# KGGR_M2.net
KiCad netlist of a schematic drawn in EAGLE
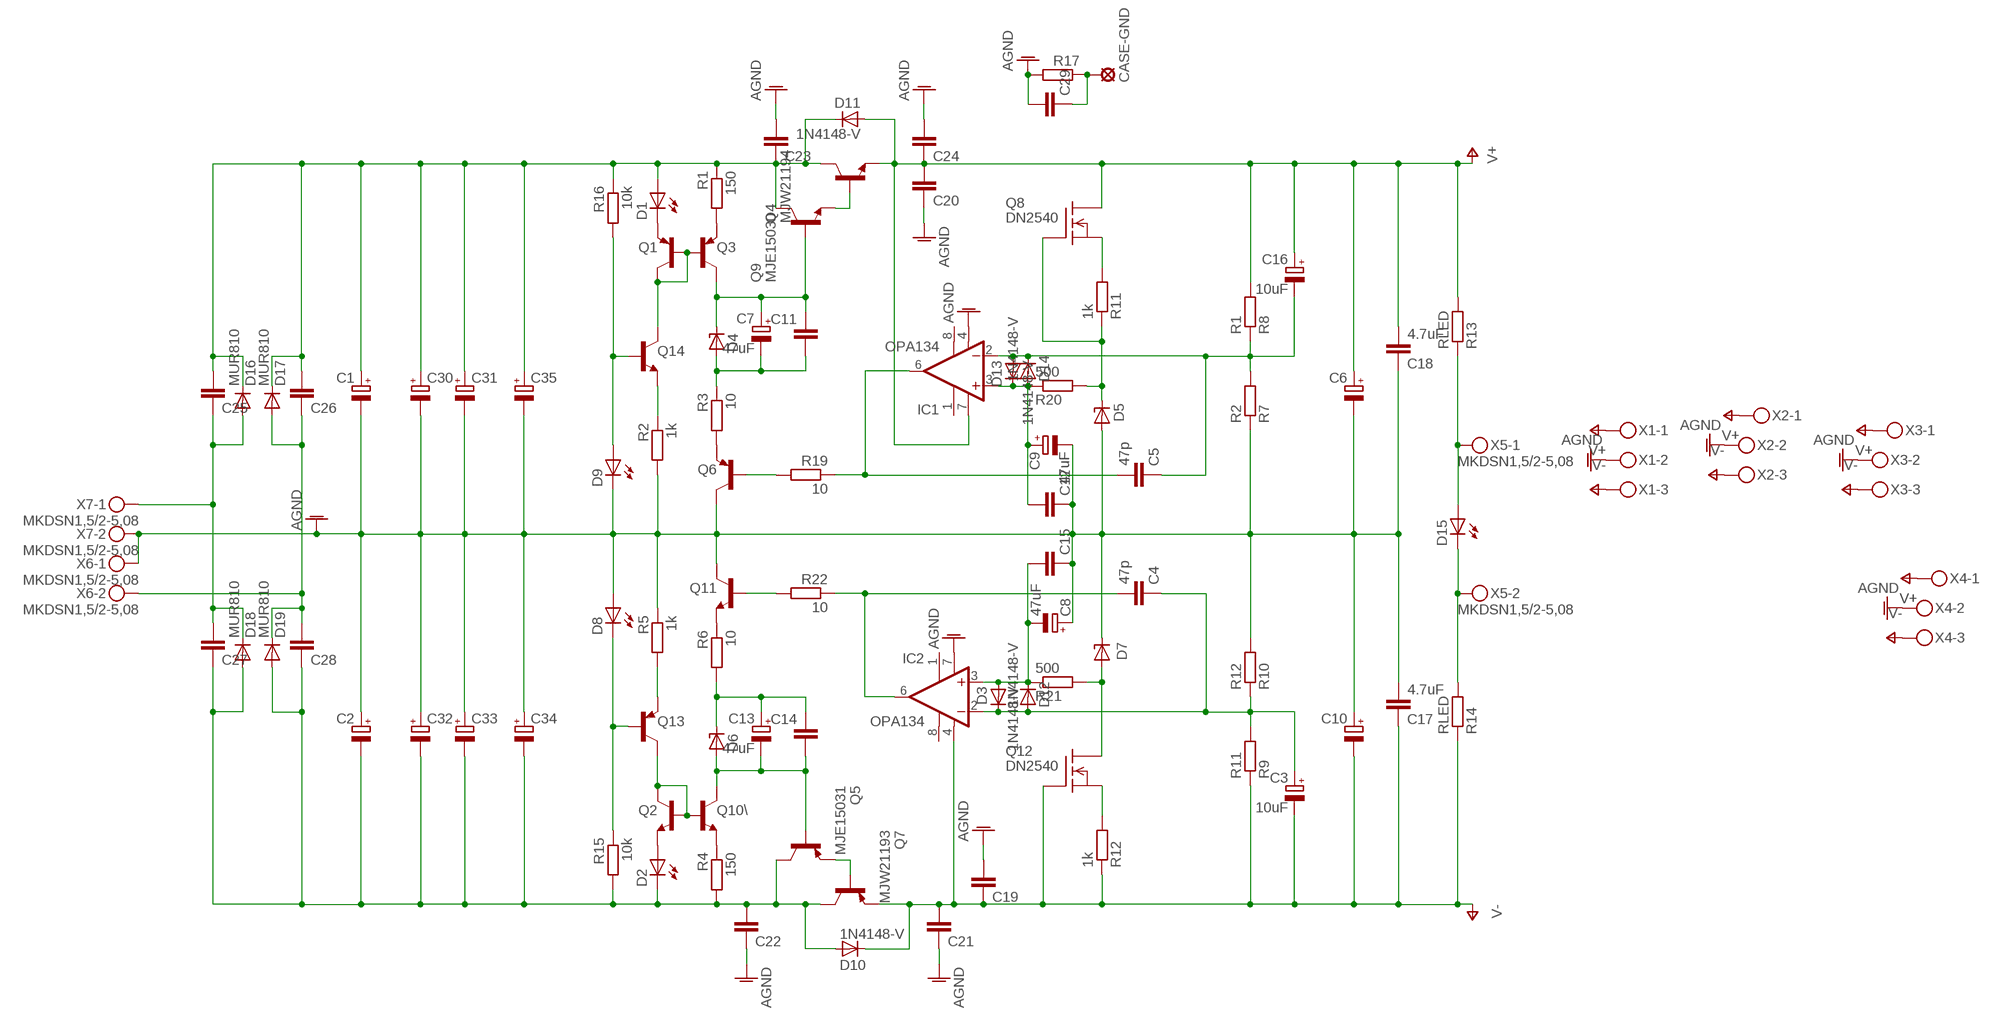
[diagram p0: schematic, sheet 1]

(export (version "E")
  (design (tool "Eeschema 10.0.6"))
  (components
    (comp (ref "C1")
      (value "CPOL-EUE10-35")
      (footprint "eagle-import:EB35D")
      (libsource (lib "eagle-import") (part "CPOL-EUE10-35"))
    )
    (comp (ref "C2")
      (value "CPOL-EUE10-35")
      (footprint "eagle-import:EB35D")
      (libsource (lib "eagle-import") (part "CPOL-EUE10-35"))
    )
    (comp (ref "C3")
      (value "10uF")
      (footprint "eagle-import:E5-8,5")
      (libsource (lib "eagle-import") (part "CPOL-EUE5-8.5"))
    )
    (comp (ref "C4")
      (value "47p")
      (footprint "eagle-import:C025_050-025X075")
      (libsource (lib "eagle-import") (part "C-EU025_050-025X075"))
    )
    (comp (ref "C5")
      (value "47p")
      (footprint "eagle-import:C025_050-025X075")
      (libsource (lib "eagle-import") (part "C-EU025_050-025X075"))
    )
    (comp (ref "C6")
      (value "CPOL-EUE7.5-18")
      (footprint "eagle-import:E7,5-18")
      (libsource (lib "eagle-import") (part "CPOL-EUE7.5-18"))
    )
    (comp (ref "C7")
      (value "47uF")
      (footprint "eagle-import:E5-8,5")
      (libsource (lib "eagle-import") (part "CPOL-EUE5-8.5"))
    )
    (comp (ref "C8")
      (value "47uF")
      (footprint "eagle-import:E5-8,5")
      (libsource (lib "eagle-import") (part "CPOL-EUE5-8.5"))
    )
    (comp (ref "C9")
      (value "47uF")
      (footprint "eagle-import:E5-8,5")
      (libsource (lib "eagle-import") (part "CPOL-EUE5-8.5"))
    )
    (comp (ref "C10")
      (value "CPOL-EUE7.5-18")
      (footprint "eagle-import:E7,5-18")
      (libsource (lib "eagle-import") (part "CPOL-EUE7.5-18"))
    )
    (comp (ref "C11")
      (value "C-EU050-035X075")
      (footprint "eagle-import:C050-035X075")
      (libsource (lib "eagle-import") (part "C-EU050-035X075"))
    )
    (comp (ref "C12")
      (value "C-EU050-035X075")
      (footprint "eagle-import:C050-035X075")
      (libsource (lib "eagle-import") (part "C-EU050-035X075"))
    )
    (comp (ref "C13")
      (value "47uF")
      (footprint "eagle-import:E5-8,5")
      (libsource (lib "eagle-import") (part "CPOL-EUE5-8.5"))
    )
    (comp (ref "C14")
      (value "C-EU050-035X075")
      (footprint "eagle-import:C050-035X075")
      (libsource (lib "eagle-import") (part "C-EU050-035X075"))
    )
    (comp (ref "C15")
      (value "C-EU050-035X075")
      (footprint "eagle-import:C050-035X075")
      (libsource (lib "eagle-import") (part "C-EU050-035X075"))
    )
    (comp (ref "C16")
      (value "10uF")
      (footprint "eagle-import:E5-8,5")
      (libsource (lib "eagle-import") (part "CPOL-EUE5-8.5"))
    )
    (comp (ref "C17")
      (value "4.7uF")
      (footprint "eagle-import:C050-075X075")
      (libsource (lib "eagle-import") (part "C-EU050-075X075"))
    )
    (comp (ref "C18")
      (value "4.7uF")
      (footprint "eagle-import:C050-075X075")
      (libsource (lib "eagle-import") (part "C-EU050-075X075"))
    )
    (comp (ref "C19")
      (value "C-EU050-035X075")
      (footprint "eagle-import:C050-035X075")
      (libsource (lib "eagle-import") (part "C-EU050-035X075"))
    )
    (comp (ref "C20")
      (value "C-EU050-035X075")
      (footprint "eagle-import:C050-035X075")
      (libsource (lib "eagle-import") (part "C-EU050-035X075"))
    )
    (comp (ref "C21")
      (value "C-EU050-035X075")
      (footprint "eagle-import:C050-035X075")
      (libsource (lib "eagle-import") (part "C-EU050-035X075"))
    )
    (comp (ref "C22")
      (value "C-EU050-075X075")
      (footprint "eagle-import:C050-075X075")
      (libsource (lib "eagle-import") (part "C-EU050-075X075"))
    )
    (comp (ref "C23")
      (value "C-EU050-075X075")
      (footprint "eagle-import:C050-075X075")
      (libsource (lib "eagle-import") (part "C-EU050-075X075"))
    )
    (comp (ref "C24")
      (value "C-EU050-035X075")
      (footprint "eagle-import:C050-035X075")
      (libsource (lib "eagle-import") (part "C-EU050-035X075"))
    )
    (comp (ref "C25")
      (value "C-EU050-035X075")
      (footprint "eagle-import:C050-035X075")
      (libsource (lib "eagle-import") (part "C-EU050-035X075"))
    )
    (comp (ref "C26")
      (value "C-EU050-035X075")
      (footprint "eagle-import:C050-035X075")
      (libsource (lib "eagle-import") (part "C-EU050-035X075"))
    )
    (comp (ref "C27")
      (value "C-EU050-035X075")
      (footprint "eagle-import:C050-035X075")
      (libsource (lib "eagle-import") (part "C-EU050-035X075"))
    )
    (comp (ref "C28")
      (value "C-EU050-035X075")
      (footprint "eagle-import:C050-035X075")
      (libsource (lib "eagle-import") (part "C-EU050-035X075"))
    )
    (comp (ref "C29")
      (value "C-EU102_152-062X184")
      (footprint "eagle-import:C102_152-062X184")
      (libsource (lib "eagle-import") (part "C-EU102_152-062X184"))
    )
    (comp (ref "C30")
      (value "CPOL-EUE7.5-18")
      (footprint "eagle-import:E7,5-18")
      (libsource (lib "eagle-import") (part "CPOL-EUE7.5-18"))
    )
    (comp (ref "C31")
      (value "CPOL-EUE7.5-18")
      (footprint "eagle-import:E7,5-18")
      (libsource (lib "eagle-import") (part "CPOL-EUE7.5-18"))
    )
    (comp (ref "C32")
      (value "CPOL-EUE7.5-18")
      (footprint "eagle-import:E7,5-18")
      (libsource (lib "eagle-import") (part "CPOL-EUE7.5-18"))
    )
    (comp (ref "C33")
      (value "CPOL-EUE7.5-18")
      (footprint "eagle-import:E7,5-18")
      (libsource (lib "eagle-import") (part "CPOL-EUE7.5-18"))
    )
    (comp (ref "C34")
      (value "CPOL-EUE7.5-18")
      (footprint "eagle-import:E7,5-18")
      (libsource (lib "eagle-import") (part "CPOL-EUE7.5-18"))
    )
    (comp (ref "C35")
      (value "CPOL-EUE7.5-18")
      (footprint "eagle-import:E7,5-18")
      (libsource (lib "eagle-import") (part "CPOL-EUE7.5-18"))
    )
    (comp (ref "CASE-GND")
      (value "SE14")
      (footprint "eagle-import:SE14")
      (libsource (lib "eagle-import") (part "SE14"))
    )
    (comp (ref "D1")
      (value "LED5MM")
      (footprint "eagle-import:LED5MM")
      (libsource (lib "eagle-import") (part "LED5MM"))
    )
    (comp (ref "D2")
      (value "LED5MM")
      (footprint "eagle-import:LED5MM")
      (libsource (lib "eagle-import") (part "LED5MM"))
    )
    (comp (ref "D3")
      (value "1N4148-V")
      (footprint "eagle-import:1N4148")
      (libsource (lib "eagle-import") (part "1N4148-V"))
    )
    (comp (ref "D4")
      (value "1N4728")
      (footprint "eagle-import:DO41Z10")
      (libsource (lib "eagle-import") (part "1N4728"))
    )
    (comp (ref "D5")
      (value "LT1021")
      (footprint "eagle-import:DIL08")
      (libsource (lib "eagle-import") (part "LT1021-V"))
    )
    (comp (ref "D6")
      (value "1N4728")
      (footprint "eagle-import:DO41Z10")
      (libsource (lib "eagle-import") (part "1N4728"))
    )
    (comp (ref "D7")
      (value "LT1021")
      (footprint "eagle-import:DIL08")
      (libsource (lib "eagle-import") (part "LT1021-V"))
    )
    (comp (ref "D8")
      (value "LED5MM")
      (footprint "eagle-import:LED5MM")
      (libsource (lib "eagle-import") (part "LED5MM"))
    )
    (comp (ref "D9")
      (value "LED5MM")
      (footprint "eagle-import:LED5MM")
      (libsource (lib "eagle-import") (part "LED5MM"))
    )
    (comp (ref "D10")
      (value "1N4148-V")
      (footprint "eagle-import:1N4148")
      (libsource (lib "eagle-import") (part "1N4148-V"))
    )
    (comp (ref "D11")
      (value "1N4148-V")
      (footprint "eagle-import:1N4148")
      (libsource (lib "eagle-import") (part "1N4148-V"))
    )
    (comp (ref "D12")
      (value "1N4148-V")
      (footprint "eagle-import:1N4148")
      (libsource (lib "eagle-import") (part "1N4148-V"))
    )
    (comp (ref "D13")
      (value "1N4148-V")
      (footprint "eagle-import:1N4148")
      (libsource (lib "eagle-import") (part "1N4148-V"))
    )
    (comp (ref "D14")
      (value "1N4148-V")
      (footprint "eagle-import:1N4148")
      (libsource (lib "eagle-import") (part "1N4148-V"))
    )
    (comp (ref "D15")
      (value "LED5MM")
      (footprint "eagle-import:LED5MM")
      (libsource (lib "eagle-import") (part "LED5MM"))
    )
    (comp (ref "D16")
      (value "MUR810")
      (footprint "eagle-import:TO220ACS")
      (libsource (lib "eagle-import") (part "MUR810"))
    )
    (comp (ref "D17")
      (value "MUR810")
      (footprint "eagle-import:TO220ACS")
      (libsource (lib "eagle-import") (part "MUR810"))
    )
    (comp (ref "D18")
      (value "MUR810")
      (footprint "eagle-import:TO220ACS")
      (libsource (lib "eagle-import") (part "MUR810"))
    )
    (comp (ref "D19")
      (value "MUR810")
      (footprint "eagle-import:TO220ACS")
      (libsource (lib "eagle-import") (part "MUR810"))
    )
    (comp (ref "IC1")
      (value "OPA134")
      (footprint "eagle-import:DIL08")
      (fields (field (name "MF") "TEXAS INSTRUMENTS") (field (name "MPN") "OPA134PA"))
      (libsource (lib "eagle-import") (part "OPA134P"))
    )
    (comp (ref "IC2")
      (value "OPA134")
      (footprint "eagle-import:DIL08")
      (fields (field (name "MF") "TEXAS INSTRUMENTS") (field (name "MPN") "OPA134PA"))
      (libsource (lib "eagle-import") (part "OPA134P"))
    )
    (comp (ref "Q1")
      (value "MPSA92-PNP-TO92-EBC")
      (footprint "eagle-import:TO92-EBC")
      (libsource (lib "eagle-import") (part "-PNP-TO92-EBCMPSA92"))
    )
    (comp (ref "Q2")
      (value "MPSA42-NPN-TO92-EBC")
      (footprint "eagle-import:TO92-EBC")
      (libsource (lib "eagle-import") (part "-NPN-TO92-EBCMPSA42"))
    )
    (comp (ref "Q3")
      (value "MPSA92-PNP-TO92-EBC")
      (footprint "eagle-import:TO92-EBC")
      (libsource (lib "eagle-import") (part "-PNP-TO92-EBCMPSA92"))
    )
    (comp (ref "Q4")
      (value "MJW21194")
      (footprint "eagle-import:TO-264")
      (libsource (lib "eagle-import") (part "MJL4281"))
    )
    (comp (ref "Q5")
      (value "MJE15031")
      (footprint "eagle-import:TO220KG")
      (libsource (lib "eagle-import") (part "MJE15031"))
    )
    (comp (ref "Q6")
      (value "MPSA92-PNP-TO92-EBC")
      (footprint "eagle-import:TO92-EBC")
      (libsource (lib "eagle-import") (part "-PNP-TO92-EBCMPSA92"))
    )
    (comp (ref "Q7")
      (value "MJW21193")
      (footprint "eagle-import:TO-264")
      (libsource (lib "eagle-import") (part "MJL4302"))
    )
    (comp (ref "Q8")
      (value "DN2540")
      (footprint "eagle-import:TO92-")
      (libsource (lib "eagle-import") (part "2N7000"))
    )
    (comp (ref "Q9")
      (value "MJE15030")
      (footprint "eagle-import:TO220KG")
      (libsource (lib "eagle-import") (part "MJE15030"))
    )
    (comp (ref "Q10\\")
      (value "MPSA42-NPN-TO92-EBC")
      (footprint "eagle-import:TO92-EBC")
      (libsource (lib "eagle-import") (part "-NPN-TO92-EBCMPSA42"))
    )
    (comp (ref "Q11")
      (value "MPSA42-NPN-TO92-EBC")
      (footprint "eagle-import:TO92-EBC")
      (libsource (lib "eagle-import") (part "-NPN-TO92-EBCMPSA42"))
    )
    (comp (ref "Q12")
      (value "DN2540")
      (footprint "eagle-import:TO92-")
      (libsource (lib "eagle-import") (part "2N7000"))
    )
    (comp (ref "Q13")
      (value "MPSA92-PNP-TO92-EBC")
      (footprint "eagle-import:TO92-EBC")
      (libsource (lib "eagle-import") (part "-PNP-TO92-EBCMPSA92"))
    )
    (comp (ref "Q14")
      (value "MPSA42-NPN-TO92-EBC")
      (footprint "eagle-import:TO92-EBC")
      (libsource (lib "eagle-import") (part "-NPN-TO92-EBCMPSA42"))
    )
    (comp (ref "R1")
      (value "150")
      (footprint "eagle-import:0309_12")
      (libsource (lib "eagle-import") (part "R-EU_0309/12"))
    )
    (comp (ref "R2")
      (value "1k")
      (footprint "eagle-import:0309_12")
      (libsource (lib "eagle-import") (part "R-EU_0309/12"))
    )
    (comp (ref "R3")
      (value "10")
      (footprint "eagle-import:0309_12")
      (libsource (lib "eagle-import") (part "R-EU_0309/12"))
    )
    (comp (ref "R4")
      (value "150")
      (footprint "eagle-import:0309_12")
      (libsource (lib "eagle-import") (part "R-EU_0309/12"))
    )
    (comp (ref "R5")
      (value "1k")
      (footprint "eagle-import:0309_12")
      (libsource (lib "eagle-import") (part "R-EU_0309/12"))
    )
    (comp (ref "R6")
      (value "10")
      (footprint "eagle-import:0309_12")
      (libsource (lib "eagle-import") (part "R-EU_0309/12"))
    )
    (comp (ref "R7")
      (value "R2")
      (footprint "eagle-import:0309_12")
      (libsource (lib "eagle-import") (part "R-EU_0309/12"))
    )
    (comp (ref "R8")
      (value "R1")
      (footprint "eagle-import:0309_12")
      (libsource (lib "eagle-import") (part "R-EU_0309/12"))
    )
    (comp (ref "R9")
      (value "R11")
      (footprint "eagle-import:0309_12")
      (libsource (lib "eagle-import") (part "R-EU_0309/12"))
    )
    (comp (ref "R10")
      (value "R12")
      (footprint "eagle-import:0309_12")
      (libsource (lib "eagle-import") (part "R-EU_0309/12"))
    )
    (comp (ref "R11")
      (value "1k")
      (footprint "eagle-import:0309_12")
      (libsource (lib "eagle-import") (part "R-EU_0309/12"))
    )
    (comp (ref "R12")
      (value "1k")
      (footprint "eagle-import:0309_12")
      (libsource (lib "eagle-import") (part "R-EU_0309/12"))
    )
    (comp (ref "R13")
      (value "RLED")
      (footprint "eagle-import:0309_12")
      (libsource (lib "eagle-import") (part "R-EU_0309/12"))
    )
    (comp (ref "R14")
      (value "RLED")
      (footprint "eagle-import:0309_12")
      (libsource (lib "eagle-import") (part "R-EU_0309/12"))
    )
    (comp (ref "R15")
      (value "10k")
      (footprint "eagle-import:0309_12")
      (libsource (lib "eagle-import") (part "R-EU_0309/12"))
    )
    (comp (ref "R16")
      (value "10k")
      (footprint "eagle-import:0309_12")
      (libsource (lib "eagle-import") (part "R-EU_0309/12"))
    )
    (comp (ref "R17")
      (value "R-EU_0617/22")
      (footprint "eagle-import:0617_22")
      (libsource (lib "eagle-import") (part "R-EU_0617/22"))
    )
    (comp (ref "R19")
      (value "10")
      (footprint "eagle-import:0309_12")
      (libsource (lib "eagle-import") (part "R-EU_0309/12"))
    )
    (comp (ref "R20")
      (value "500")
      (footprint "eagle-import:0309_12")
      (libsource (lib "eagle-import") (part "R-EU_0309/12"))
    )
    (comp (ref "R21")
      (value "500")
      (footprint "eagle-import:0309_12")
      (libsource (lib "eagle-import") (part "R-EU_0309/12"))
    )
    (comp (ref "R22")
      (value "10")
      (footprint "eagle-import:0309_12")
      (libsource (lib "eagle-import") (part "R-EU_0309/12"))
    )
    (comp (ref "X1")
      (value "MKDSN1,5/3-5,08")
      (footprint "eagle-import:MKDSN1,5_3-5,08")
      (libsource (lib "eagle-import") (part "MKDSN1,5/3-5,08"))
    )
    (comp (ref "X2")
      (value "MKDSN1,5/3-5,08")
      (footprint "eagle-import:MKDSN1,5_3-5,08")
      (libsource (lib "eagle-import") (part "MKDSN1,5/3-5,08"))
    )
    (comp (ref "X3")
      (value "MKDSN1,5/3-5,08")
      (footprint "eagle-import:MKDSN1,5_3-5,08")
      (libsource (lib "eagle-import") (part "MKDSN1,5/3-5,08"))
    )
    (comp (ref "X4")
      (value "MKDSN1,5/3-5,08")
      (footprint "eagle-import:MKDSN1,5_3-5,08")
      (libsource (lib "eagle-import") (part "MKDSN1,5/3-5,08"))
    )
    (comp (ref "X5")
      (value "MKDSN1,5/2-5,08")
      (footprint "eagle-import:MKDSN1,5_2-5,08")
      (libsource (lib "eagle-import") (part "MKDSN1,5/2-5,08"))
    )
    (comp (ref "X6")
      (value "MKDSN1,5/2-5,08")
      (footprint "eagle-import:MKDSN1,5_2-5,08")
      (libsource (lib "eagle-import") (part "MKDSN1,5/2-5,08"))
    )
    (comp (ref "X7")
      (value "MKDSN1,5/2-5,08")
      (footprint "eagle-import:MKDSN1,5_2-5,08")
      (libsource (lib "eagle-import") (part "MKDSN1,5/2-5,08"))
    )
  )
  (nets
    (net (code "1") (name "AGND") (class "Default")
      (node (ref "C1") (pin "-") (pinfunction "-_-") (pintype "passive"))
      (node (ref "C10") (pin "+") (pinfunction "+_+") (pintype "passive"))
      (node (ref "C12") (pin "1") (pinfunction "1_1") (pintype "passive"))
      (node (ref "C15") (pin "1") (pinfunction "1_1") (pintype "passive"))
      (node (ref "C17") (pin "2") (pinfunction "2_2") (pintype "passive"))
      (node (ref "C18") (pin "1") (pinfunction "1_1") (pintype "passive"))
      (node (ref "C19") (pin "2") (pinfunction "2_2") (pintype "passive"))
      (node (ref "C2") (pin "+") (pinfunction "+_+") (pintype "passive"))
      (node (ref "C20") (pin "1") (pinfunction "1_1") (pintype "passive"))
      (node (ref "C21") (pin "1") (pinfunction "1_1") (pintype "passive"))
      (node (ref "C22") (pin "1") (pinfunction "1_1") (pintype "passive"))
      (node (ref "C23") (pin "2") (pinfunction "2_2") (pintype "passive"))
      (node (ref "C24") (pin "2") (pinfunction "2_2") (pintype "passive"))
      (node (ref "C29") (pin "2") (pinfunction "2_2") (pintype "passive"))
      (node (ref "C29") (pin "3") (pinfunction "2_3") (pintype "passive"))
      (node (ref "C30") (pin "-") (pinfunction "-_-") (pintype "passive"))
      (node (ref "C31") (pin "-") (pinfunction "-_-") (pintype "passive"))
      (node (ref "C32") (pin "+") (pinfunction "+_+") (pintype "passive"))
      (node (ref "C33") (pin "+") (pinfunction "+_+") (pintype "passive"))
      (node (ref "C34") (pin "+") (pinfunction "+_+") (pintype "passive"))
      (node (ref "C35") (pin "-") (pinfunction "-_-") (pintype "passive"))
      (node (ref "C6") (pin "-") (pinfunction "-_-") (pintype "passive"))
      (node (ref "C8") (pin "+") (pinfunction "+_+") (pintype "passive"))
      (node (ref "C9") (pin "-") (pinfunction "-_-") (pintype "passive"))
      (node (ref "D5") (pin "4") (pinfunction "GND_4") (pintype "passive"))
      (node (ref "D7") (pin "6") (pinfunction "OUT_6") (pintype "passive"))
      (node (ref "D8") (pin "A") (pinfunction "A_A") (pintype "passive"))
      (node (ref "D9") (pin "K") (pinfunction "C_K") (pintype "passive"))
      (node (ref "IC1") (pin "4") (pinfunction "V-_4") (pintype "power_in"))
      (node (ref "IC2") (pin "7") (pinfunction "V+_7") (pintype "power_in"))
      (node (ref "Q11") (pin "C") (pinfunction "C_C") (pintype "passive"))
      (node (ref "Q6") (pin "C") (pinfunction "C_C") (pintype "passive"))
      (node (ref "R10") (pin "2") (pinfunction "2_2") (pintype "passive"))
      (node (ref "R17") (pin "2") (pinfunction "2_2") (pintype "passive"))
      (node (ref "R2") (pin "2") (pinfunction "2_2") (pintype "passive"))
      (node (ref "R5") (pin "1") (pinfunction "1_1") (pintype "passive"))
      (node (ref "R7") (pin "1") (pinfunction "1_1") (pintype "passive"))
      (node (ref "X1") (pin "2") (pinfunction "KL_2") (pintype "passive"))
      (node (ref "X2") (pin "2") (pinfunction "KL_2") (pintype "passive"))
      (node (ref "X3") (pin "2") (pinfunction "KL_2") (pintype "passive"))
      (node (ref "X4") (pin "2") (pinfunction "KL_2") (pintype "passive"))
      (node (ref "X6") (pin "1") (pinfunction "KL_1") (pintype "passive"))
      (node (ref "X7") (pin "2") (pinfunction "KL_2") (pintype "passive"))
    )
    (net (code "2") (name "Net-(C11-Pad2)") (class "Default")
      (node (ref "C11") (pin "2") (pinfunction "2_2") (pintype "passive"))
      (node (ref "C7") (pin "-") (pinfunction "-_-") (pintype "passive"))
      (node (ref "D4") (pin "A") (pinfunction "A_A") (pintype "passive"))
      (node (ref "R3") (pin "1") (pinfunction "1_1") (pintype "passive"))
    )
    (net (code "3") (name "Net-(C13-Pad+)") (class "Default")
      (node (ref "C13") (pin "+") (pinfunction "+_+") (pintype "passive"))
      (node (ref "C14") (pin "1") (pinfunction "1_1") (pintype "passive"))
      (node (ref "D6") (pin "C") (pinfunction "C_C") (pintype "passive"))
      (node (ref "R6") (pin "2") (pinfunction "2_2") (pintype "passive"))
    )
    (net (code "4") (name "Net-(C29-Pad1)") (class "Default")
      (node (ref "C29") (pin "1") (pinfunction "1_1") (pintype "passive"))
      (node (ref "CASE-GND") (pin "MP") (pinfunction "MP_MP") (pintype "passive"))
      (node (ref "R17") (pin "1") (pinfunction "1_1") (pintype "passive"))
    )
    (net (code "5") (name "Net-(D1-C)") (class "Default")
      (node (ref "D1") (pin "K") (pinfunction "C_K") (pintype "passive"))
      (node (ref "Q1") (pin "E") (pinfunction "E_E") (pintype "passive"))
    )
    (net (code "6") (name "Net-(D2-C)") (class "Default")
      (node (ref "C2") (pin "-") (pinfunction "-_-") (pintype "passive"))
      (node (ref "C22") (pin "2") (pinfunction "2_2") (pintype "passive"))
      (node (ref "C27") (pin "1") (pinfunction "1_1") (pintype "passive"))
      (node (ref "C28") (pin "1") (pinfunction "1_1") (pintype "passive"))
      (node (ref "C32") (pin "-") (pinfunction "-_-") (pintype "passive"))
      (node (ref "C33") (pin "-") (pinfunction "-_-") (pintype "passive"))
      (node (ref "C34") (pin "-") (pinfunction "-_-") (pintype "passive"))
      (node (ref "D10") (pin "A") (pinfunction "A_A") (pintype "passive"))
      (node (ref "D18") (pin "A") (pinfunction "A_A") (pintype "passive"))
      (node (ref "D19") (pin "A") (pinfunction "A_A") (pintype "passive"))
      (node (ref "D2") (pin "K") (pinfunction "C_K") (pintype "passive"))
      (node (ref "Q5") (pin "2") (pinfunction "C_2") (pintype "passive"))
      (node (ref "Q7") (pin "C") (pinfunction "C_C") (pintype "passive"))
      (node (ref "R15") (pin "2") (pinfunction "2_2") (pintype "passive"))
      (node (ref "R4") (pin "2") (pinfunction "2_2") (pintype "passive"))
    )
    (net (code "7") (name "Net-(D2-PadA)") (class "Default")
      (node (ref "D2") (pin "A") (pinfunction "A_A") (pintype "passive"))
      (node (ref "Q2") (pin "E") (pinfunction "E_E") (pintype "passive"))
    )
    (net (code "8") (name "Net-(D5-OUT)") (class "Default")
      (node (ref "D5") (pin "6") (pinfunction "OUT_6") (pintype "passive"))
      (node (ref "Q8") (pin "2") (pinfunction "G_2") (pintype "passive"))
      (node (ref "R11") (pin "1") (pinfunction "1_1") (pintype "passive"))
      (node (ref "R20") (pin "2") (pinfunction "2_2") (pintype "passive"))
    )
    (net (code "9") (name "Net-(D7-GND)") (class "Default")
      (node (ref "D7") (pin "4") (pinfunction "GND_4") (pintype "passive"))
      (node (ref "Q12") (pin "1") (pinfunction "D_1") (pintype "passive"))
      (node (ref "R21") (pin "2") (pinfunction "2_2") (pintype "passive"))
    )
    (net (code "10") (name "Net-(D8-C)") (class "Default")
      (node (ref "D8") (pin "K") (pinfunction "C_K") (pintype "passive"))
      (node (ref "Q13") (pin "B") (pinfunction "B_B") (pintype "passive"))
      (node (ref "R15") (pin "1") (pinfunction "1_1") (pintype "passive"))
    )
    (net (code "11") (name "Net-(D9-PadA)") (class "Default")
      (node (ref "D9") (pin "A") (pinfunction "A_A") (pintype "passive"))
      (node (ref "Q14") (pin "B") (pinfunction "B_B") (pintype "passive"))
      (node (ref "R16") (pin "2") (pinfunction "2_2") (pintype "passive"))
    )
    (net (code "12") (name "Net-(D15-C)") (class "Default")
      (node (ref "D15") (pin "K") (pinfunction "C_K") (pintype "passive"))
      (node (ref "R14") (pin "2") (pinfunction "2_2") (pintype "passive"))
      (node (ref "X5") (pin "2") (pinfunction "KL_2") (pintype "passive"))
    )
    (net (code "13") (name "Net-(IC1-+IN)") (class "Default")
      (node (ref "C12") (pin "2") (pinfunction "2_2") (pintype "passive"))
      (node (ref "C9") (pin "+") (pinfunction "+_+") (pintype "passive"))
      (node (ref "D13") (pin "C") (pinfunction "C_C") (pintype "passive"))
      (node (ref "D14") (pin "A") (pinfunction "A_A") (pintype "passive"))
      (node (ref "IC1") (pin "3") (pinfunction "+IN_3") (pintype "input"))
      (node (ref "R20") (pin "1") (pinfunction "1_1") (pintype "passive"))
    )
    (net (code "14") (name "Net-(IC1--IN)") (class "Default")
      (node (ref "C16") (pin "-") (pinfunction "-_-") (pintype "passive"))
      (node (ref "C5") (pin "1") (pinfunction "1_1") (pintype "passive"))
      (node (ref "D13") (pin "A") (pinfunction "A_A") (pintype "passive"))
      (node (ref "D14") (pin "C") (pinfunction "C_C") (pintype "passive"))
      (node (ref "IC1") (pin "2") (pinfunction "-IN_2") (pintype "input"))
      (node (ref "R7") (pin "2") (pinfunction "2_2") (pintype "passive"))
      (node (ref "R8") (pin "1") (pinfunction "1_1") (pintype "passive"))
    )
    (net (code "15") (name "Net-(IC1-OUT)") (class "Default")
      (node (ref "C5") (pin "2") (pinfunction "2_2") (pintype "passive"))
      (node (ref "C5") (pin "3") (pinfunction "2_3") (pintype "passive"))
      (node (ref "IC1") (pin "6") (pinfunction "OUT_6") (pintype "output"))
      (node (ref "R19") (pin "1") (pinfunction "1_1") (pintype "passive"))
    )
    (net (code "16") (name "Net-(IC2-+IN)") (class "Default")
      (node (ref "C15") (pin "2") (pinfunction "2_2") (pintype "passive"))
      (node (ref "C8") (pin "-") (pinfunction "-_-") (pintype "passive"))
      (node (ref "D12") (pin "C") (pinfunction "C_C") (pintype "passive"))
      (node (ref "D3") (pin "A") (pinfunction "A_A") (pintype "passive"))
      (node (ref "IC2") (pin "3") (pinfunction "+IN_3") (pintype "input"))
      (node (ref "R21") (pin "1") (pinfunction "1_1") (pintype "passive"))
    )
    (net (code "17") (name "Net-(IC2--IN)") (class "Default")
      (node (ref "C3") (pin "+") (pinfunction "+_+") (pintype "passive"))
      (node (ref "C4") (pin "1") (pinfunction "1_1") (pintype "passive"))
      (node (ref "D12") (pin "A") (pinfunction "A_A") (pintype "passive"))
      (node (ref "D3") (pin "C") (pinfunction "C_C") (pintype "passive"))
      (node (ref "IC2") (pin "2") (pinfunction "-IN_2") (pintype "input"))
      (node (ref "R10") (pin "1") (pinfunction "1_1") (pintype "passive"))
      (node (ref "R9") (pin "2") (pinfunction "2_2") (pintype "passive"))
    )
    (net (code "18") (name "Net-(IC2-OUT)") (class "Default")
      (node (ref "C4") (pin "2") (pinfunction "2_2") (pintype "passive"))
      (node (ref "C4") (pin "3") (pinfunction "2_3") (pintype "passive"))
      (node (ref "IC2") (pin "6") (pinfunction "OUT_6") (pintype "output"))
      (node (ref "R22") (pin "1") (pinfunction "1_1") (pintype "passive"))
    )
    (net (code "19") (name "Net-(Q1-PadB)") (class "Default")
      (node (ref "Q1") (pin "B") (pinfunction "B_B") (pintype "passive"))
      (node (ref "Q1") (pin "C") (pinfunction "C_C") (pintype "passive"))
      (node (ref "Q14") (pin "C") (pinfunction "C_C") (pintype "passive"))
      (node (ref "Q3") (pin "B") (pinfunction "B_B") (pintype "passive"))
    )
    (net (code "20") (name "Net-(Q3-PadE)") (class "Default")
      (node (ref "Q3") (pin "E") (pinfunction "E_E") (pintype "passive"))
      (node (ref "R1") (pin "2") (pinfunction "2_2") (pintype "passive"))
    )
    (net (code "21") (name "Net-(Q5-B)") (class "Default")
      (node (ref "C13") (pin "-") (pinfunction "-_-") (pintype "passive"))
      (node (ref "C14") (pin "2") (pinfunction "2_2") (pintype "passive"))
      (node (ref "D6") (pin "A") (pinfunction "A_A") (pintype "passive"))
      (node (ref "Q10\\") (pin "C") (pinfunction "C_C") (pintype "passive"))
      (node (ref "Q5") (pin "1") (pinfunction "B_1") (pintype "passive"))
    )
    (net (code "22") (name "Net-(Q5-E)") (class "Default")
      (node (ref "Q5") (pin "3") (pinfunction "E_3") (pintype "passive"))
      (node (ref "Q7") (pin "B") (pinfunction "B_B") (pintype "passive"))
    )
    (net (code "23") (name "Net-(Q6-PadB)") (class "Default")
      (node (ref "Q6") (pin "B") (pinfunction "B_B") (pintype "passive"))
      (node (ref "R19") (pin "2") (pinfunction "2_2") (pintype "passive"))
    )
    (net (code "24") (name "Net-(Q6-PadE)") (class "Default")
      (node (ref "Q6") (pin "E") (pinfunction "E_E") (pintype "passive"))
      (node (ref "R3") (pin "2") (pinfunction "2_2") (pintype "passive"))
    )
    (net (code "25") (name "Net-(Q8-S)") (class "Default")
      (node (ref "Q8") (pin "3") (pinfunction "S_3") (pintype "passive"))
      (node (ref "R11") (pin "2") (pinfunction "2_2") (pintype "passive"))
    )
    (net (code "26") (name "Net-(Q9-B)") (class "Default")
      (node (ref "C11") (pin "1") (pinfunction "1_1") (pintype "passive"))
      (node (ref "C7") (pin "+") (pinfunction "+_+") (pintype "passive"))
      (node (ref "D4") (pin "C") (pinfunction "C_C") (pintype "passive"))
      (node (ref "Q3") (pin "C") (pinfunction "C_C") (pintype "passive"))
      (node (ref "Q9") (pin "1") (pinfunction "B_1") (pintype "passive"))
    )
    (net (code "27") (name "Net-(Q9-C)") (class "Default")
      (node (ref "C1") (pin "+") (pinfunction "+_+") (pintype "passive"))
      (node (ref "C23") (pin "1") (pinfunction "1_1") (pintype "passive"))
      (node (ref "C25") (pin "2") (pinfunction "2_2") (pintype "passive"))
      (node (ref "C26") (pin "2") (pinfunction "2_2") (pintype "passive"))
      (node (ref "C30") (pin "+") (pinfunction "+_+") (pintype "passive"))
      (node (ref "C31") (pin "+") (pinfunction "+_+") (pintype "passive"))
      (node (ref "C35") (pin "+") (pinfunction "+_+") (pintype "passive"))
      (node (ref "D1") (pin "A") (pinfunction "A_A") (pintype "passive"))
      (node (ref "D11") (pin "C") (pinfunction "C_C") (pintype "passive"))
      (node (ref "D16") (pin "C") (pinfunction "C_C") (pintype "passive"))
      (node (ref "D17") (pin "C") (pinfunction "C_C") (pintype "passive"))
      (node (ref "Q4") (pin "C") (pinfunction "C_C") (pintype "passive"))
      (node (ref "Q9") (pin "2") (pinfunction "C_2") (pintype "passive"))
      (node (ref "R1") (pin "1") (pinfunction "1_1") (pintype "passive"))
      (node (ref "R16") (pin "1") (pinfunction "1_1") (pintype "passive"))
    )
    (net (code "28") (name "Net-(Q9-E)") (class "Default")
      (node (ref "Q4") (pin "B") (pinfunction "B_B") (pintype "passive"))
      (node (ref "Q9") (pin "3") (pinfunction "E_3") (pintype "passive"))
    )
    (net (code "29") (name "Net-(Q10\\-PadB)") (class "Default")
      (node (ref "Q10\\") (pin "B") (pinfunction "B_B") (pintype "passive"))
      (node (ref "Q13") (pin "C") (pinfunction "C_C") (pintype "passive"))
      (node (ref "Q2") (pin "B") (pinfunction "B_B") (pintype "passive"))
      (node (ref "Q2") (pin "C") (pinfunction "C_C") (pintype "passive"))
    )
    (net (code "30") (name "Net-(Q10\\-PadE)") (class "Default")
      (node (ref "Q10\\") (pin "E") (pinfunction "E_E") (pintype "passive"))
      (node (ref "R4") (pin "1") (pinfunction "1_1") (pintype "passive"))
    )
    (net (code "31") (name "Net-(Q11-PadB)") (class "Default")
      (node (ref "Q11") (pin "B") (pinfunction "B_B") (pintype "passive"))
      (node (ref "R22") (pin "2") (pinfunction "2_2") (pintype "passive"))
    )
    (net (code "32") (name "Net-(Q11-PadE)") (class "Default")
      (node (ref "Q11") (pin "E") (pinfunction "E_E") (pintype "passive"))
      (node (ref "R6") (pin "1") (pinfunction "1_1") (pintype "passive"))
    )
    (net (code "33") (name "Net-(Q12-S)") (class "Default")
      (node (ref "Q12") (pin "3") (pinfunction "S_3") (pintype "passive"))
      (node (ref "R12") (pin "2") (pinfunction "2_2") (pintype "passive"))
    )
    (net (code "34") (name "Net-(Q13-PadE)") (class "Default")
      (node (ref "Q13") (pin "E") (pinfunction "E_E") (pintype "passive"))
      (node (ref "R5") (pin "2") (pinfunction "2_2") (pintype "passive"))
    )
    (net (code "35") (name "Net-(Q14-PadE)") (class "Default")
      (node (ref "Q14") (pin "E") (pinfunction "E_E") (pintype "passive"))
      (node (ref "R2") (pin "1") (pinfunction "1_1") (pintype "passive"))
    )
    (net (code "36") (name "Net-(X5A-KL)") (class "Default")
      (node (ref "D15") (pin "A") (pinfunction "A_A") (pintype "passive"))
      (node (ref "R13") (pin "1") (pinfunction "1_1") (pintype "passive"))
      (node (ref "X5") (pin "1") (pinfunction "KL_1") (pintype "passive"))
    )
    (net (code "37") (name "Net-(X6B-KL)") (class "Default")
      (node (ref "C26") (pin "1") (pinfunction "1_1") (pintype "passive"))
      (node (ref "C28") (pin "2") (pinfunction "2_2") (pintype "passive"))
      (node (ref "D17") (pin "A") (pinfunction "A_A") (pintype "passive"))
      (node (ref "D19") (pin "C") (pinfunction "C_C") (pintype "passive"))
      (node (ref "X6") (pin "2") (pinfunction "KL_2") (pintype "passive"))
    )
    (net (code "38") (name "Net-(X7A-KL)") (class "Default")
      (node (ref "C25") (pin "1") (pinfunction "1_1") (pintype "passive"))
      (node (ref "C27") (pin "2") (pinfunction "2_2") (pintype "passive"))
      (node (ref "D16") (pin "A") (pinfunction "A_A") (pintype "passive"))
      (node (ref "D18") (pin "C") (pinfunction "C_C") (pintype "passive"))
      (node (ref "X7") (pin "1") (pinfunction "KL_1") (pintype "passive"))
    )
    (net (code "39") (name "V+") (class "Default")
      (node (ref "C16") (pin "+") (pinfunction "+_+") (pintype "passive"))
      (node (ref "C18") (pin "2") (pinfunction "2_2") (pintype "passive"))
      (node (ref "C20") (pin "2") (pinfunction "2_2") (pintype "passive"))
      (node (ref "C24") (pin "1") (pinfunction "1_1") (pintype "passive"))
      (node (ref "C6") (pin "+") (pinfunction "+_+") (pintype "passive"))
      (node (ref "D11") (pin "A") (pinfunction "A_A") (pintype "passive"))
      (node (ref "IC1") (pin "7") (pinfunction "V+_7") (pintype "power_in"))
      (node (ref "Q4") (pin "E") (pinfunction "E_E") (pintype "passive"))
      (node (ref "Q8") (pin "1") (pinfunction "D_1") (pintype "passive"))
      (node (ref "R13") (pin "2") (pinfunction "2_2") (pintype "passive"))
      (node (ref "R8") (pin "2") (pinfunction "2_2") (pintype "passive"))
      (node (ref "X1") (pin "1") (pinfunction "KL_1") (pintype "passive"))
      (node (ref "X2") (pin "1") (pinfunction "KL_1") (pintype "passive"))
      (node (ref "X3") (pin "1") (pinfunction "KL_1") (pintype "passive"))
      (node (ref "X4") (pin "1") (pinfunction "KL_1") (pintype "passive"))
    )
    (net (code "40") (name "V-") (class "Default")
      (node (ref "C10") (pin "-") (pinfunction "-_-") (pintype "passive"))
      (node (ref "C17") (pin "1") (pinfunction "1_1") (pintype "passive"))
      (node (ref "C19") (pin "1") (pinfunction "1_1") (pintype "passive"))
      (node (ref "C21") (pin "2") (pinfunction "2_2") (pintype "passive"))
      (node (ref "C3") (pin "-") (pinfunction "-_-") (pintype "passive"))
      (node (ref "D10") (pin "C") (pinfunction "C_C") (pintype "passive"))
      (node (ref "IC2") (pin "4") (pinfunction "V-_4") (pintype "power_in"))
      (node (ref "Q12") (pin "2") (pinfunction "G_2") (pintype "passive"))
      (node (ref "Q7") (pin "E") (pinfunction "E_E") (pintype "passive"))
      (node (ref "R12") (pin "1") (pinfunction "1_1") (pintype "passive"))
      (node (ref "R14") (pin "1") (pinfunction "1_1") (pintype "passive"))
      (node (ref "R9") (pin "1") (pinfunction "1_1") (pintype "passive"))
      (node (ref "X1") (pin "3") (pinfunction "KL_3") (pintype "passive"))
      (node (ref "X2") (pin "3") (pinfunction "KL_3") (pintype "passive"))
      (node (ref "X3") (pin "3") (pinfunction "KL_3") (pintype "passive"))
      (node (ref "X4") (pin "3") (pinfunction "KL_3") (pintype "passive"))
    )
    (net (code "41") (name "unconnected-(IC1-TRIM1-Pad1)") (class "Default")
      (node (ref "IC1") (pin "1") (pinfunction "TRIM1_1") (pintype "passive"))
    )
    (net (code "42") (name "unconnected-(IC1-TRIM2-Pad8)") (class "Default")
      (node (ref "IC1") (pin "8") (pinfunction "TRIM2_8") (pintype "passive"))
    )
    (net (code "43") (name "unconnected-(IC2-TRIM1-Pad1)") (class "Default")
      (node (ref "IC2") (pin "1") (pinfunction "TRIM1_1") (pintype "passive"))
    )
    (net (code "44") (name "unconnected-(IC2-TRIM2-Pad8)") (class "Default")
      (node (ref "IC2") (pin "8") (pinfunction "TRIM2_8") (pintype "passive"))
    )
  )
)
